# Main_Board.net
KiCad netlist of a schematic drawn in EAGLE
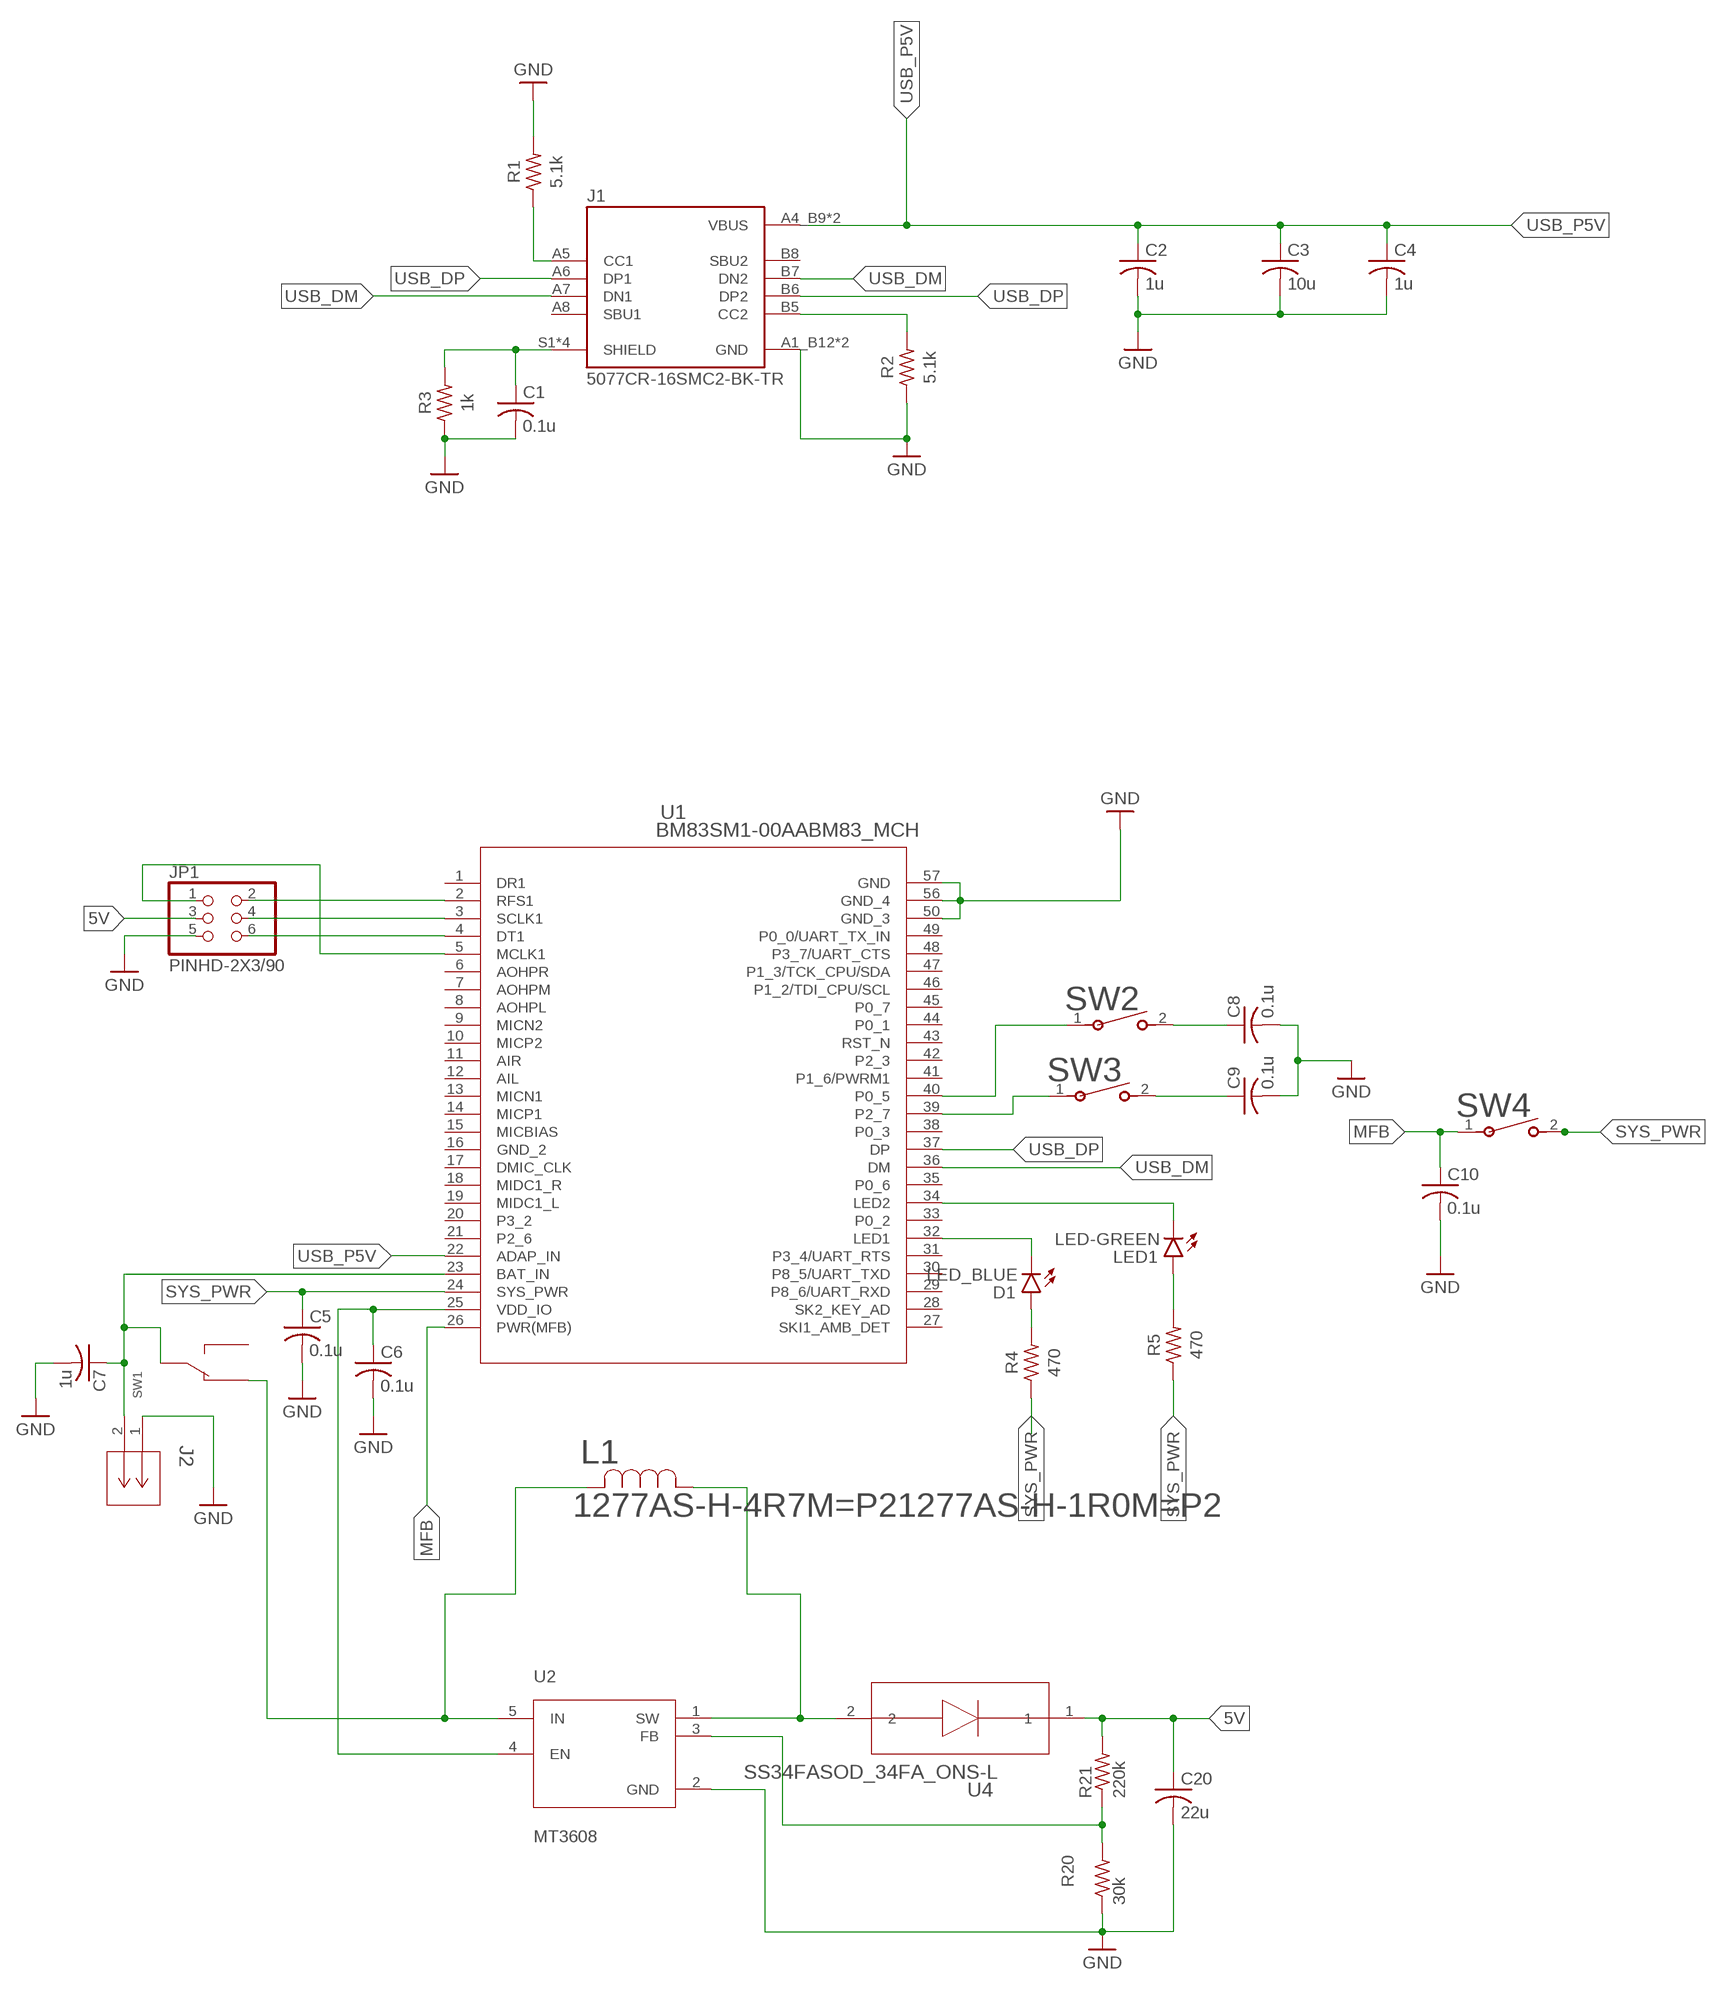
[diagram p0: schematic, sheet 1]

(export (version "E")
  (design (tool "Eeschema 10.0.6"))
  (components
    (comp (ref "C1")
      (value "0.1u")
      (footprint "eagle-import:CAPC1608X85")
      (libsource (lib "eagle-import") (part "C-USCHIP-0603(1608-METRIC)_"))
    )
    (comp (ref "C2")
      (value "1u")
      (footprint "eagle-import:CAPC1608X85")
      (libsource (lib "eagle-import") (part "C-USCHIP-0603(1608-METRIC)_"))
    )
    (comp (ref "C3")
      (value "10u")
      (footprint "eagle-import:CAPC1608X85")
      (libsource (lib "eagle-import") (part "C-USCHIP-0603(1608-METRIC)_"))
    )
    (comp (ref "C4")
      (value "1u")
      (footprint "eagle-import:CAPC1608X85")
      (libsource (lib "eagle-import") (part "C-USCHIP-0603(1608-METRIC)_"))
    )
    (comp (ref "C5")
      (value "0.1u")
      (footprint "eagle-import:CAPC1608X85")
      (libsource (lib "eagle-import") (part "C-USCHIP-0603(1608-METRIC)_"))
    )
    (comp (ref "C6")
      (value "0.1u")
      (footprint "eagle-import:CAPC1608X85")
      (libsource (lib "eagle-import") (part "C-USCHIP-0603(1608-METRIC)_"))
    )
    (comp (ref "C7")
      (value "1u")
      (footprint "eagle-import:CAPC1608X85")
      (libsource (lib "eagle-import") (part "C-USCHIP-0603(1608-METRIC)_"))
    )
    (comp (ref "C8")
      (value "0.1u")
      (footprint "eagle-import:CAPC1608X85")
      (libsource (lib "eagle-import") (part "C-USCHIP-0603(1608-METRIC)_"))
    )
    (comp (ref "C9")
      (value "0.1u")
      (footprint "eagle-import:CAPC1608X85")
      (libsource (lib "eagle-import") (part "C-USCHIP-0603(1608-METRIC)_"))
    )
    (comp (ref "C10")
      (value "0.1u")
      (footprint "eagle-import:CAPC1608X85")
      (libsource (lib "eagle-import") (part "C-USCHIP-0603(1608-METRIC)_"))
    )
    (comp (ref "C20")
      (value "22u")
      (footprint "eagle-import:CAPC3216X135")
      (libsource (lib "eagle-import") (part "C-USCHIP-1206(3216-METRIC)_"))
    )
    (comp (ref "D1")
      (value "LED_BLUE")
      (footprint "eagle-import:LEDC1608X39N_B")
      (libsource (lib "eagle-import") (part "LED_CHIPBLUE-1608_"))
    )
    (comp (ref "J1")
      (value "5077CR-16SMC2-BK-TR")
      (footprint "eagle-import:NELTRON_5077CR-16SMC2-BK-TR")
      (fields (field (name "MF") "Neltron"))
      (libsource (lib "eagle-import") (part "5077CR-16SMC2-BK-TR"))
    )
    (comp (ref "J2")
      (value "S2B-PH-K-S(LF)(SN)")
      (footprint "eagle-import:CONN_S2B-PH-K-S_JST")
      (fields (field (name "COPYRIGHT") "Copyright (C) 2024 Ultra Librarian. All rights reserved."))
      (libsource (lib "eagle-import") (part "S2B-PH-K-S(LF)(SN)"))
    )
    (comp (ref "JP1")
      (value "PINHD-2X3/90")
      (footprint "eagle-import:2X03_90")
      (fields (field (name "MANUFACTURER") "Generic"))
      (libsource (lib "eagle-import") (part "PINHD-2X3/90"))
    )
    (comp (ref "L1")
      (value "1277AS-H-4R7M=P21277AS-H-1R0M=P2")
      (footprint "eagle-import:1277AS-H-1R0M=P2")
      (fields
        (field (name "MANUFACTURER_PART_NUMBER") "1277AS-H-4R7M=P2")
        (field (name "COPYRIGHT") "Copyright (C) 2024 Ultra Librarian. All rights reserved.")
      )
      (libsource (lib "eagle-import") (part "1277AS-H-4R7M=P21277AS-H-1R0M=P2"))
    )
    (comp (ref "LED1")
      (value "LED-GREEN")
      (footprint "eagle-import:LEDC1608X39N_G")
      (libsource (lib "eagle-import") (part "Tutorial - Fusion 360_16997205_LED_CHIPGREEN-1608_"))
    )
    (comp (ref "R1")
      (value "5.1k")
      (footprint "eagle-import:RESC1608X60")
      (libsource (lib "eagle-import") (part "R-USCHIP-0603(1608-METRIC)_"))
    )
    (comp (ref "R2")
      (value "5.1k")
      (footprint "eagle-import:RESC1608X60")
      (libsource (lib "eagle-import") (part "R-USCHIP-0603(1608-METRIC)_"))
    )
    (comp (ref "R3")
      (value "1k")
      (footprint "eagle-import:RESC1608X60")
      (libsource (lib "eagle-import") (part "R-USCHIP-0603(1608-METRIC)_"))
    )
    (comp (ref "R4")
      (value "470")
      (footprint "eagle-import:RESC1608X60")
      (libsource (lib "eagle-import") (part "R-USCHIP-0603(1608-METRIC)_"))
    )
    (comp (ref "R5")
      (value "470")
      (footprint "eagle-import:RESC1608X60")
      (libsource (lib "eagle-import") (part "R-USCHIP-0603(1608-METRIC)_"))
    )
    (comp (ref "R20")
      (value "30k")
      (footprint "eagle-import:RESC1608X60")
      (libsource (lib "eagle-import") (part "Tutorial - Fusion 360_16997205_R-USCHIP-0603(1608-METRIC)_"))
    )
    (comp (ref "R21")
      (value "220k")
      (footprint "eagle-import:RESC1608X60")
      (libsource (lib "eagle-import") (part "Tutorial - Fusion 360_16997205_R-USCHIP-0603(1608-METRIC)_"))
    )
    (comp (ref "SW1")
      (value "MMS124")
      (footprint "eagle-import:MMS124")
      (libsource (lib "eagle-import") (part "MMS124"))
    )
    (comp (ref "SW2")
      (value "EVP-AKE31ASW_EVP-AKE31A_PAN")
      (footprint "eagle-import:SW_EVP-AKE31A_PAN")
      (fields
        (field (name "MANUFACTURER_PART_NUMBER") "EVP-AKE31A")
        (field (name "COPYRIGHT") "Copyright (C) 2024 Ultra Librarian. All rights reserved.")
      )
      (libsource (lib "eagle-import") (part "EVP-AKE31ASW_EVP-AKE31A_PAN"))
    )
    (comp (ref "SW3")
      (value "EVP-AKE31ASW_EVP-AKE31A_PAN")
      (footprint "eagle-import:SW_EVP-AKE31A_PAN")
      (fields
        (field (name "MANUFACTURER_PART_NUMBER") "EVP-AKE31A")
        (field (name "COPYRIGHT") "Copyright (C) 2024 Ultra Librarian. All rights reserved.")
      )
      (libsource (lib "eagle-import") (part "EVP-AKE31ASW_EVP-AKE31A_PAN"))
    )
    (comp (ref "SW4")
      (value "EVP-AKE31ASW_EVP-AKE31A_PAN")
      (footprint "eagle-import:SW_EVP-AKE31A_PAN")
      (fields
        (field (name "MANUFACTURER_PART_NUMBER") "EVP-AKE31A")
        (field (name "COPYRIGHT") "Copyright (C) 2024 Ultra Librarian. All rights reserved.")
      )
      (libsource (lib "eagle-import") (part "EVP-AKE31ASW_EVP-AKE31A_PAN"))
    )
    (comp (ref "U1")
      (value "BM83SM1-00AABM83_MCH")
      (footprint "eagle-import:BM83_MCH")
      (fields
        (field (name "MANUFACTURER_PART_NUMBER") "BM83SM1-00AA")
        (field (name "COPYRIGHT") "Copyright (C) 2024 Ultra Librarian. All rights reserved.")
      )
      (libsource (lib "eagle-import") (part "BM83SM1-00AABM83_MCH"))
    )
    (comp (ref "U2")
      (value "MT3608")
      (footprint "eagle-import:SOT95P280X145-6N")
      (fields (field (name "MF") "Aerosemi Technology Co., Ltd"))
      (libsource (lib "eagle-import") (part "MT3608"))
    )
    (comp (ref "U4")
      (value "SS34FASOD_34FA_ONS-L")
      (footprint "eagle-import:SOD_34FA_ONS-L")
      (fields
        (field (name "MANUFACTURER_PART_NUMBER") "SS34FA")
        (field (name "COPYRIGHT") "Copyright (C) 2024 Ultra Librarian. All rights reserved.")
      )
      (libsource (lib "eagle-import") (part "SS34FASOD_34FA_ONS-L"))
    )
  )
  (nets
    (net (code "1") (name "/MICBIAS") (class "Default")
      (node (ref "U1") (pin "15") (pinfunction "MICBIAS_15") (pintype "power_in"))
    )
    (net (code "2") (name "5V") (class "Default")
      (node (ref "C20") (pin "1") (pinfunction "1_1") (pintype "passive"))
      (node (ref "JP1") (pin "3") (pinfunction "3_3") (pintype "passive"))
      (node (ref "R21") (pin "2") (pinfunction "2_2") (pintype "passive"))
      (node (ref "U4") (pin "1") (pinfunction "1_1") (pintype "passive"))
    )
    (net (code "3") (name "GND") (class "Default")
      (node (ref "C1") (pin "2") (pinfunction "2_2") (pintype "passive"))
      (node (ref "C10") (pin "2") (pinfunction "2_2") (pintype "passive"))
      (node (ref "C2") (pin "2") (pinfunction "2_2") (pintype "passive"))
      (node (ref "C20") (pin "2") (pinfunction "2_2") (pintype "passive"))
      (node (ref "C3") (pin "2") (pinfunction "2_2") (pintype "passive"))
      (node (ref "C4") (pin "2") (pinfunction "2_2") (pintype "passive"))
      (node (ref "C5") (pin "2") (pinfunction "2_2") (pintype "passive"))
      (node (ref "C6") (pin "2") (pinfunction "2_2") (pintype "passive"))
      (node (ref "C7") (pin "2") (pinfunction "2_2") (pintype "passive"))
      (node (ref "C8") (pin "2") (pinfunction "2_2") (pintype "passive"))
      (node (ref "C9") (pin "2") (pinfunction "2_2") (pintype "passive"))
      (node (ref "J1") (pin "A1_B12") (pinfunction "GND_A1_B12") (pintype "power_in"))
      (node (ref "J1") (pin "B1_A12") (pinfunction "GND_B1_A12") (pintype "power_in"))
      (node (ref "J2") (pin "1") (pinfunction "1_1") (pintype "passive"))
      (node (ref "JP1") (pin "5") (pinfunction "5_5") (pintype "passive"))
      (node (ref "R1") (pin "2") (pinfunction "2_2") (pintype "passive"))
      (node (ref "R2") (pin "1") (pinfunction "1_1") (pintype "passive"))
      (node (ref "R20") (pin "1") (pinfunction "1_1") (pintype "passive"))
      (node (ref "R3") (pin "1") (pinfunction "1_1") (pintype "passive"))
      (node (ref "U1") (pin "50") (pinfunction "GND_3_50") (pintype "passive"))
      (node (ref "U1") (pin "56") (pinfunction "GND_4_56") (pintype "passive"))
      (node (ref "U1") (pin "57") (pinfunction "GND_57") (pintype "passive"))
      (node (ref "U2") (pin "2") (pinfunction "GND_2") (pintype "power_in"))
    )
    (net (code "4") (name "MFB") (class "Default")
      (node (ref "C10") (pin "1") (pinfunction "1_1") (pintype "passive"))
      (node (ref "SW4") (pin "1") (pinfunction "1_1") (pintype "passive"))
      (node (ref "U1") (pin "26") (pinfunction "PWR(MFB)_26") (pintype "input"))
    )
    (net (code "5") (name "Net-(C1-Pad1)") (class "Default")
      (node (ref "C1") (pin "1") (pinfunction "1_1") (pintype "passive"))
      (node (ref "J1") (pin "S1") (pinfunction "SHIELD_S1") (pintype "passive"))
      (node (ref "J1") (pin "S2") (pinfunction "SHIELD_S2") (pintype "passive"))
      (node (ref "J1") (pin "S3") (pinfunction "SHIELD_S3") (pintype "passive"))
      (node (ref "J1") (pin "S4") (pinfunction "SHIELD_S4") (pintype "passive"))
      (node (ref "R3") (pin "2") (pinfunction "2_2") (pintype "passive"))
    )
    (net (code "6") (name "Net-(C8-Pad1)") (class "Default")
      (node (ref "C8") (pin "1") (pinfunction "1_1") (pintype "passive"))
      (node (ref "SW2") (pin "2") (pinfunction "2_2") (pintype "passive"))
    )
    (net (code "7") (name "Net-(C9-Pad1)") (class "Default")
      (node (ref "C9") (pin "1") (pinfunction "1_1") (pintype "passive"))
      (node (ref "SW3") (pin "2") (pinfunction "2_2") (pintype "passive"))
    )
    (net (code "8") (name "Net-(D1-A)") (class "Default")
      (node (ref "D1") (pin "2") (pinfunction "A_2") (pintype "passive"))
      (node (ref "R4") (pin "2") (pinfunction "2_2") (pintype "passive"))
    )
    (net (code "9") (name "Net-(D1-C)") (class "Default")
      (node (ref "D1") (pin "1") (pinfunction "C_1") (pintype "passive"))
      (node (ref "U1") (pin "32") (pinfunction "LED1_32") (pintype "input"))
    )
    (net (code "10") (name "Net-(J1-CC1)") (class "Default")
      (node (ref "J1") (pin "A5") (pinfunction "CC1_A5") (pintype "passive"))
      (node (ref "R1") (pin "1") (pinfunction "1_1") (pintype "passive"))
    )
    (net (code "11") (name "Net-(J1-CC2)") (class "Default")
      (node (ref "J1") (pin "B5") (pinfunction "CC2_B5") (pintype "passive"))
      (node (ref "R2") (pin "2") (pinfunction "2_2") (pintype "passive"))
    )
    (net (code "12") (name "Net-(LED1-A)") (class "Default")
      (node (ref "LED1") (pin "2") (pinfunction "A_2") (pintype "passive"))
      (node (ref "R5") (pin "2") (pinfunction "2_2") (pintype "passive"))
    )
    (net (code "13") (name "Net-(LED1-C)") (class "Default")
      (node (ref "LED1") (pin "1") (pinfunction "C_1") (pintype "passive"))
      (node (ref "U1") (pin "34") (pinfunction "LED2_34") (pintype "input"))
    )
    (net (code "14") (name "Net-(SW1-2)") (class "Default")
      (node (ref "C7") (pin "1") (pinfunction "1_1") (pintype "passive"))
      (node (ref "J2") (pin "2") (pinfunction "2_2") (pintype "passive"))
      (node (ref "SW1") (pin "3") (pinfunction "2_3") (pintype "bidirectional"))
      (node (ref "U1") (pin "23") (pinfunction "BAT_IN_23") (pintype "power_in"))
    )
    (net (code "15") (name "Net-(U1-DT1)") (class "Default")
      (node (ref "JP1") (pin "6") (pinfunction "6_6") (pintype "passive"))
      (node (ref "U1") (pin "4") (pinfunction "DT1_4") (pintype "output"))
    )
    (net (code "16") (name "Net-(U1-MCLK1)") (class "Default")
      (node (ref "JP1") (pin "1") (pinfunction "1_1") (pintype "passive"))
      (node (ref "U1") (pin "5") (pinfunction "MCLK1_5") (pintype "output"))
    )
    (net (code "17") (name "Net-(U1-P0_5)") (class "Default")
      (node (ref "SW2") (pin "1") (pinfunction "1_1") (pintype "passive"))
      (node (ref "U1") (pin "40") (pinfunction "P0_5_40") (pintype "bidirectional"))
    )
    (net (code "18") (name "Net-(U1-P2_7)") (class "Default")
      (node (ref "SW3") (pin "1") (pinfunction "1_1") (pintype "passive"))
      (node (ref "U1") (pin "39") (pinfunction "P2_7_39") (pintype "bidirectional"))
    )
    (net (code "19") (name "Net-(U1-RFS1)") (class "Default")
      (node (ref "JP1") (pin "2") (pinfunction "2_2") (pintype "passive"))
      (node (ref "U1") (pin "2") (pinfunction "RFS1_2") (pintype "bidirectional"))
    )
    (net (code "20") (name "Net-(U1-SCLK1)") (class "Default")
      (node (ref "JP1") (pin "4") (pinfunction "4_4") (pintype "passive"))
      (node (ref "U1") (pin "3") (pinfunction "SCLK1_3") (pintype "bidirectional"))
    )
    (net (code "21") (name "Net-(U1-VDD_IO)") (class "Default")
      (node (ref "C6") (pin "1") (pinfunction "1_1") (pintype "passive"))
      (node (ref "U1") (pin "25") (pinfunction "VDD_IO_25") (pintype "power_in"))
      (node (ref "U2") (pin "4") (pinfunction "EN_4") (pintype "input"))
    )
    (net (code "22") (name "Net-(U2-FB)") (class "Default")
      (node (ref "R20") (pin "2") (pinfunction "2_2") (pintype "passive"))
      (node (ref "R21") (pin "1") (pinfunction "1_1") (pintype "passive"))
      (node (ref "U2") (pin "3") (pinfunction "FB_3") (pintype "input"))
    )
    (net (code "23") (name "Net-(U2-IN)") (class "Default")
      (node (ref "L1") (pin "2") (pinfunction "2_2") (pintype "passive"))
      (node (ref "SW1") (pin "1") (pinfunction "1_1") (pintype "bidirectional"))
      (node (ref "U2") (pin "5") (pinfunction "IN_5") (pintype "input"))
    )
    (net (code "24") (name "Net-(U2-SW)") (class "Default")
      (node (ref "L1") (pin "1") (pinfunction "1_1") (pintype "passive"))
      (node (ref "U2") (pin "1") (pinfunction "SW_1") (pintype "output"))
      (node (ref "U4") (pin "2") (pinfunction "2_2") (pintype "passive"))
    )
    (net (code "25") (name "SYS_PWR") (class "Default")
      (node (ref "C5") (pin "1") (pinfunction "1_1") (pintype "passive"))
      (node (ref "R4") (pin "1") (pinfunction "1_1") (pintype "passive"))
      (node (ref "R5") (pin "1") (pinfunction "1_1") (pintype "passive"))
      (node (ref "SW4") (pin "2") (pinfunction "2_2") (pintype "passive"))
      (node (ref "U1") (pin "24") (pinfunction "SYS_PWR_24") (pintype "power_in"))
    )
    (net (code "26") (name "USB_DM") (class "Default")
      (node (ref "J1") (pin "A7") (pinfunction "DN1_A7") (pintype "passive"))
      (node (ref "J1") (pin "B7") (pinfunction "DN2_B7") (pintype "passive"))
      (node (ref "U1") (pin "36") (pinfunction "DM_36") (pintype "bidirectional"))
    )
    (net (code "27") (name "USB_DP") (class "Default")
      (node (ref "J1") (pin "A6") (pinfunction "DP1_A6") (pintype "passive"))
      (node (ref "J1") (pin "B6") (pinfunction "DP2_B6") (pintype "passive"))
      (node (ref "U1") (pin "37") (pinfunction "DP_37") (pintype "bidirectional"))
    )
    (net (code "28") (name "USB_P5V") (class "Default")
      (node (ref "C2") (pin "1") (pinfunction "1_1") (pintype "passive"))
      (node (ref "C3") (pin "1") (pinfunction "1_1") (pintype "passive"))
      (node (ref "C4") (pin "1") (pinfunction "1_1") (pintype "passive"))
      (node (ref "J1") (pin "A4_B9") (pinfunction "VBUS_A4_B9") (pintype "power_in"))
      (node (ref "J1") (pin "B4_A9") (pinfunction "VBUS_B4_A9") (pintype "power_in"))
      (node (ref "U1") (pin "22") (pinfunction "ADAP_IN_22") (pintype "power_in"))
    )
    (net (code "29") (name "unconnected-(J1-SBU1-PadA8)") (class "Default")
      (node (ref "J1") (pin "A8") (pinfunction "SBU1_A8") (pintype "passive"))
    )
    (net (code "30") (name "unconnected-(J1-SBU2-PadB8)") (class "Default")
      (node (ref "J1") (pin "B8") (pinfunction "SBU2_B8") (pintype "passive"))
    )
    (net (code "31") (name "unconnected-(SW1-3-Pad2)") (class "Default")
      (node (ref "SW1") (pin "2") (pinfunction "3_2") (pintype "bidirectional"))
    )
    (net (code "32") (name "unconnected-(U1-AIL-Pad12)") (class "Default")
      (node (ref "U1") (pin "12") (pinfunction "AIL_12") (pintype "input"))
    )
    (net (code "33") (name "unconnected-(U1-AIR-Pad11)") (class "Default")
      (node (ref "U1") (pin "11") (pinfunction "AIR_11") (pintype "input"))
    )
    (net (code "34") (name "unconnected-(U1-AOHPL-Pad8)") (class "Default")
      (node (ref "U1") (pin "8") (pinfunction "AOHPL_8") (pintype "output"))
    )
    (net (code "35") (name "unconnected-(U1-AOHPM-Pad7)") (class "Default")
      (node (ref "U1") (pin "7") (pinfunction "AOHPM_7") (pintype "output"))
    )
    (net (code "36") (name "unconnected-(U1-AOHPR-Pad6)") (class "Default")
      (node (ref "U1") (pin "6") (pinfunction "AOHPR_6") (pintype "output"))
    )
    (net (code "37") (name "unconnected-(U1-DMIC_CLK-Pad17)") (class "Default")
      (node (ref "U1") (pin "17") (pinfunction "DMIC_CLK_17") (pintype "output"))
    )
    (net (code "38") (name "unconnected-(U1-DR1-Pad1)") (class "Default")
      (node (ref "U1") (pin "1") (pinfunction "DR1_1") (pintype "input"))
    )
    (net (code "39") (name "unconnected-(U1-GND_2-Pad16)") (class "Default")
      (node (ref "U1") (pin "16") (pinfunction "GND_2_16") (pintype "passive"))
    )
    (net (code "40") (name "unconnected-(U1-MICN1-Pad13)") (class "Default")
      (node (ref "U1") (pin "13") (pinfunction "MICN1_13") (pintype "input"))
    )
    (net (code "41") (name "unconnected-(U1-MICN2-Pad9)") (class "Default")
      (node (ref "U1") (pin "9") (pinfunction "MICN2_9") (pintype "input"))
    )
    (net (code "42") (name "unconnected-(U1-MICP1-Pad14)") (class "Default")
      (node (ref "U1") (pin "14") (pinfunction "MICP1_14") (pintype "input"))
    )
    (net (code "43") (name "unconnected-(U1-MICP2-Pad10)") (class "Default")
      (node (ref "U1") (pin "10") (pinfunction "MICP2_10") (pintype "input"))
    )
    (net (code "44") (name "unconnected-(U1-MIDC1_L-Pad19)") (class "Default")
      (node (ref "U1") (pin "19") (pinfunction "MIDC1_L_19") (pintype "input"))
    )
    (net (code "45") (name "unconnected-(U1-MIDC1_R-Pad18)") (class "Default")
      (node (ref "U1") (pin "18") (pinfunction "MIDC1_R_18") (pintype "input"))
    )
    (net (code "46") (name "unconnected-(U1-P0_0{slash}UART_TX_IN-Pad49)") (class "Default")
      (node (ref "U1") (pin "49") (pinfunction "P0_0/UART_TX_IN_49") (pintype "bidirectional"))
    )
    (net (code "47") (name "unconnected-(U1-P0_1-Pad44)") (class "Default")
      (node (ref "U1") (pin "44") (pinfunction "P0_1_44") (pintype "bidirectional"))
    )
    (net (code "48") (name "unconnected-(U1-P0_2-Pad33)") (class "Default")
      (node (ref "U1") (pin "33") (pinfunction "P0_2_33") (pintype "bidirectional"))
    )
    (net (code "49") (name "unconnected-(U1-P0_3-Pad38)") (class "Default")
      (node (ref "U1") (pin "38") (pinfunction "P0_3_38") (pintype "bidirectional"))
    )
    (net (code "50") (name "unconnected-(U1-P0_6-Pad35)") (class "Default")
      (node (ref "U1") (pin "35") (pinfunction "P0_6_35") (pintype "bidirectional"))
    )
    (net (code "51") (name "unconnected-(U1-P0_7-Pad45)") (class "Default")
      (node (ref "U1") (pin "45") (pinfunction "P0_7_45") (pintype "bidirectional"))
    )
    (net (code "52") (name "unconnected-(U1-P1_2{slash}TDI_CPU{slash}SCL-Pad46)") (class "Default")
      (node (ref "U1") (pin "46") (pinfunction "P1_2/TDI_CPU/SCL_46") (pintype "bidirectional"))
    )
    (net (code "53") (name "unconnected-(U1-P1_3{slash}TCK_CPU{slash}SDA-Pad47)") (class "Default")
      (node (ref "U1") (pin "47") (pinfunction "P1_3/TCK_CPU/SDA_47") (pintype "bidirectional"))
    )
    (net (code "54") (name "unconnected-(U1-P1_6{slash}PWRM1-Pad41)") (class "Default")
      (node (ref "U1") (pin "41") (pinfunction "P1_6/PWRM1_41") (pintype "bidirectional"))
    )
    (net (code "55") (name "unconnected-(U1-P2_3-Pad42)") (class "Default")
      (node (ref "U1") (pin "42") (pinfunction "P2_3_42") (pintype "bidirectional"))
    )
    (net (code "56") (name "unconnected-(U1-P2_6-Pad21)") (class "Default")
      (node (ref "U1") (pin "21") (pinfunction "P2_6_21") (pintype "bidirectional"))
    )
    (net (code "57") (name "unconnected-(U1-P3_2-Pad20)") (class "Default")
      (node (ref "U1") (pin "20") (pinfunction "P3_2_20") (pintype "bidirectional"))
    )
    (net (code "58") (name "unconnected-(U1-P3_4{slash}UART_RTS-Pad31)") (class "Default")
      (node (ref "U1") (pin "31") (pinfunction "P3_4/UART_RTS_31") (pintype "bidirectional"))
    )
    (net (code "59") (name "unconnected-(U1-P3_7{slash}UART_CTS-Pad48)") (class "Default")
      (node (ref "U1") (pin "48") (pinfunction "P3_7/UART_CTS_48") (pintype "bidirectional"))
    )
    (net (code "60") (name "unconnected-(U1-P8_5{slash}UART_TXD-Pad30)") (class "Default")
      (node (ref "U1") (pin "30") (pinfunction "P8_5/UART_TXD_30") (pintype "bidirectional"))
    )
    (net (code "61") (name "unconnected-(U1-P8_6{slash}UART_RXD-Pad29)") (class "Default")
      (node (ref "U1") (pin "29") (pinfunction "P8_6/UART_RXD_29") (pintype "bidirectional"))
    )
    (net (code "62") (name "unconnected-(U1-RST_N-Pad43)") (class "Default")
      (node (ref "U1") (pin "43") (pinfunction "RST_N_43") (pintype "input"))
    )
    (net (code "63") (name "unconnected-(U1-SK2_KEY_AD-Pad28)") (class "Default")
      (node (ref "U1") (pin "28") (pinfunction "SK2_KEY_AD_28") (pintype "input"))
    )
    (net (code "64") (name "unconnected-(U1-SKI1_AMB_DET-Pad27)") (class "Default")
      (node (ref "U1") (pin "27") (pinfunction "SKI1_AMB_DET_27") (pintype "input"))
    )
  )
)
